# 2.net
KiCad netlist of a schematic drawn in Altium Designer
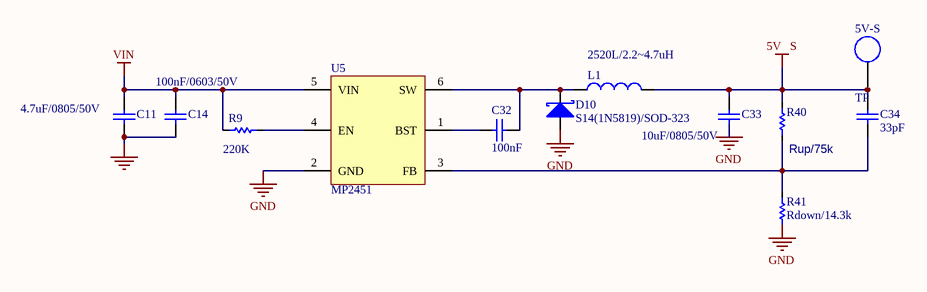
[diagram p0: (2).SchDoc]

(export (version "E")
  (design (tool "Eeschema 10.0.6"))
  (components
    (comp (ref "5V-S") (value "TP") (libsource (lib "袁琦越(2）") (part "?")))
    (comp (ref "C11")
      (value "4.7uF/0805/50V")
      (footprint "0603C")
      (description "Capacitor")
      (fields (field (name "PUBLISHER") "Altium Limited"))
      (libsource (lib "mycomponents") (part "Cap"))
    )
    (comp (ref "C14")
      (value "100nF/0603/50V")
      (footprint "0603C")
      (description "Capacitor")
      (fields (field (name "PUBLISHER") "Altium Limited"))
      (libsource (lib "mycomponents") (part "Cap"))
    )
    (comp (ref "C32")
      (value "100nF")
      (footprint "0603C")
      (description "Capacitor")
      (fields (field (name "PUBLISHER") "Altium Limited"))
      (libsource (lib "mycomponents") (part "Cap"))
    )
    (comp (ref "C33")
      (value "10uF/0805/50V")
      (footprint "0603C")
      (description "Capacitor")
      (fields (field (name "PUBLISHER") "Altium Limited"))
      (libsource (lib "mycomponents") (part "Cap"))
    )
    (comp (ref "C34")
      (value "33pF")
      (footprint "0603C")
      (description "Capacitor")
      (fields (field (name "PUBLISHER") "Altium Limited"))
      (libsource (lib "mycomponents") (part "Cap"))
    )
    (comp (ref "D10")
      (value "S14(1N5819)/SOD-323")
      (footprint "SMA/DO-214AC")
      (description "Schottky Diode")
      (fields (field (name "PUBLISHER") "Altium Limited"))
      (libsource (lib "mycomponents") (part "D Schottky_SOD323"))
    )
    (comp (ref "L1")
      (value "2520L/2.2~4.7uH")
      (footprint "0420L")
      (description "Inductor")
      (fields (field (name "PUBLISHER") "Altium Limited"))
      (libsource (lib "mycomponents") (part "Inductor"))
    )
    (comp (ref "R9")
      (value "220K")
      (footprint "0603R")
      (description "Resistor")
      (fields (field (name "PUBLISHER") "Altium Limited"))
      (libsource (lib "mycomponents") (part "Res1"))
    )
    (comp (ref "R40")
      (value "Rup/75k")
      (footprint "0603R")
      (description "Resistor")
      (fields (field (name "PUBLISHER") "Altium Limited"))
      (libsource (lib "mycomponents") (part "Res1"))
    )
    (comp (ref "R41")
      (value "Rdown/14.3k")
      (footprint "0603R")
      (description "Resistor")
      (fields (field (name "PUBLISHER") "Altium Limited"))
      (libsource (lib "mycomponents") (part "Res1"))
    )
    (comp (ref "U5")
      (value "MP2451")
      (footprint "SOT23-6L")
      (description "开关电源0.6A")
      (libsource (lib "mycomponents") (part "MP2451"))
    )
  )
  (nets
    (net (code "1") (name "5V   S") (class "Default")
      (node (ref "5V-S") (pin "1") (pinfunction "1_1") (pintype "passive"))
      (node (ref "C33") (pin "2") (pinfunction "2_2") (pintype "passive"))
      (node (ref "C34") (pin "2") (pinfunction "2_2") (pintype "passive"))
      (node (ref "L1") (pin "2") (pinfunction "2_2") (pintype "passive"))
      (node (ref "R40") (pin "2") (pinfunction "2_2") (pintype "passive"))
    )
    (net (code "2") (name "GND") (class "Default")
      (node (ref "C11") (pin "1") (pinfunction "1_1") (pintype "passive"))
      (node (ref "C14") (pin "1") (pinfunction "1_1") (pintype "passive"))
      (node (ref "C33") (pin "1") (pinfunction "1_1") (pintype "passive"))
      (node (ref "D10") (pin "1") (pinfunction "1_1") (pintype "passive"))
      (node (ref "U5") (pin "2") (pinfunction "GND_2") (pintype "passive"))
    )
    (net (code "3") (name "Net-(U5-BST)") (class "Default")
      (node (ref "C32") (pin "1") (pinfunction "1_1") (pintype "passive"))
      (node (ref "U5") (pin "1") (pinfunction "BST_1") (pintype "passive"))
    )
    (net (code "4") (name "Net-(U5-EN)") (class "Default")
      (node (ref "R9") (pin "2") (pinfunction "2_2") (pintype "passive"))
      (node (ref "U5") (pin "4") (pinfunction "EN_4") (pintype "passive"))
    )
    (net (code "5") (name "Net-(U5-FB)") (class "Default")
      (node (ref "C34") (pin "1") (pinfunction "1_1") (pintype "passive"))
      (node (ref "R40") (pin "1") (pinfunction "1_1") (pintype "passive"))
      (node (ref "R41") (pin "2") (pinfunction "2_2") (pintype "passive"))
      (node (ref "U5") (pin "3") (pinfunction "FB_3") (pintype "passive"))
    )
    (net (code "6") (name "Net-(U5-SW)") (class "Default")
      (node (ref "C32") (pin "2") (pinfunction "2_2") (pintype "passive"))
      (node (ref "D10") (pin "2") (pinfunction "2_2") (pintype "passive"))
      (node (ref "L1") (pin "1") (pinfunction "1_1") (pintype "passive"))
      (node (ref "U5") (pin "6") (pinfunction "SW_6") (pintype "passive"))
    )
    (net (code "7") (name "VIN") (class "Default")
      (node (ref "C11") (pin "2") (pinfunction "2_2") (pintype "passive"))
      (node (ref "C14") (pin "2") (pinfunction "2_2") (pintype "passive"))
      (node (ref "R9") (pin "1") (pinfunction "1_1") (pintype "passive"))
      (node (ref "U5") (pin "5") (pinfunction "VIN_5") (pintype "passive"))
    )
    (net (code "8") (name "unconnected-(R41-Pad1)") (class "Default")
      (node (ref "R41") (pin "1") (pinfunction "1_1") (pintype "passive"))
    )
  )
)
